# SCH_ATOM-Sumo_2026-06-13.net
KiCad netlist of a schematic drawn in EasyEDA
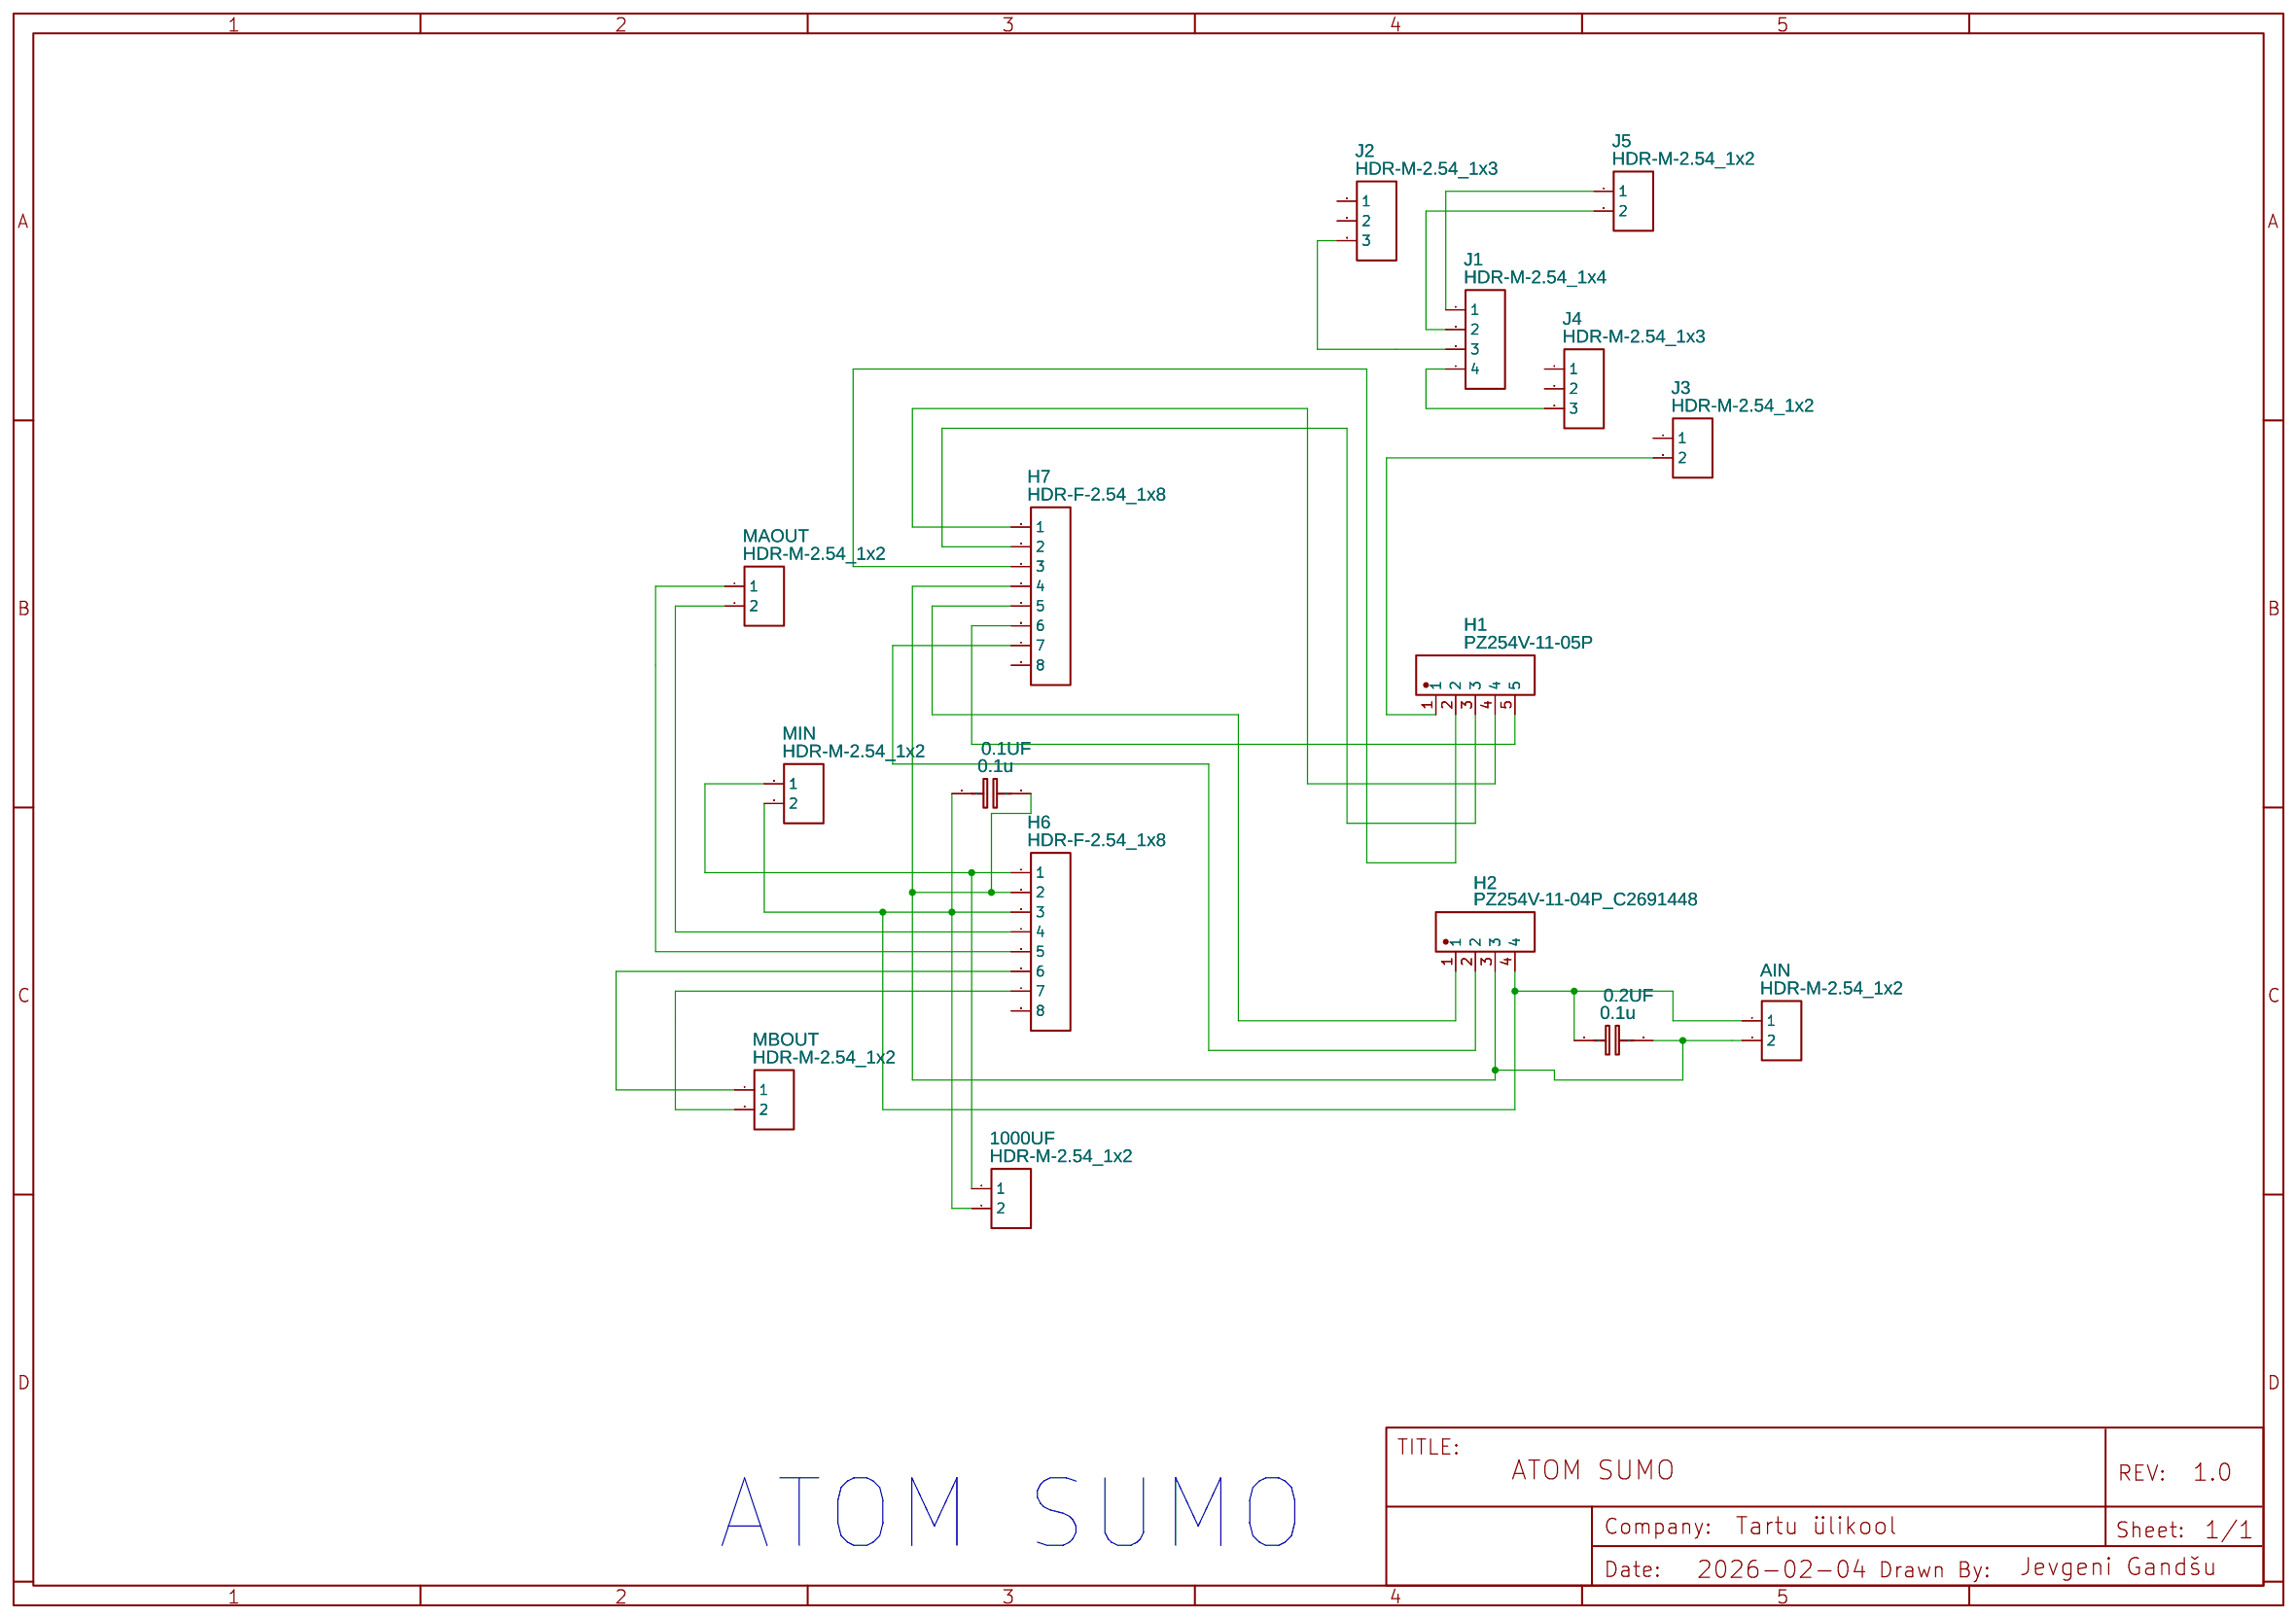
[diagram p0: schematic sheet]

(export (version "E")
  (design (tool "Eeschema 10.0.6"))
  (components
    (comp (ref "0.1UF") (value "0.1u") (libsource (lib "") (part "C_0805_EU")))
    (comp (ref "0.2UF") (value "0.1u") (libsource (lib "") (part "C_0805_EU_1")))
    (comp (ref "1000UF") (value "HDR-M-2.54_1x2") (libsource (lib "") (part "HDR-M-2.54_1x2_1")))
    (comp (ref "AIN") (value "HDR-M-2.54_1x2") (libsource (lib "") (part "HDR-M-2.54_1x2")))
    (comp (ref "H1")
      (value "PZ254V-11-05P")
      (fields (field (name "Manufacturer") "XFCN(兴飞)"))
      (libsource (lib "") (part "PZ254V-11-05P"))
    )
    (comp (ref "H2")
      (value "PZ254V-11-04P_C2691448")
      (fields (field (name "Manufacturer Part") "PZ254V-11-04P") (field (name "Manufacturer") "XFCN(兴飞)"))
      (libsource (lib "") (part "PZ254V-11-04P_C2691448"))
    )
    (comp (ref "H6") (value "HDR-F-2.54_1x8") (libsource (lib "") (part "HDR-F-2.54_1x8")))
    (comp (ref "H7") (value "HDR-F-2.54_1x8") (libsource (lib "") (part "HDR-F-2.54_1x8")))
    (comp (ref "J1") (value "HDR-M-2.54_1x4") (libsource (lib "") (part "HDR-M-2.54_1x4")))
    (comp (ref "J2") (value "HDR-M-2.54_1x3") (libsource (lib "") (part "HDR-M-2.54_1x3")))
    (comp (ref "J3") (value "HDR-M-2.54_1x2") (libsource (lib "") (part "HDR-M-2.54_1x2_3")))
    (comp (ref "J4") (value "HDR-M-2.54_1x3") (libsource (lib "") (part "HDR-M-2.54_1x3")))
    (comp (ref "J5") (value "HDR-M-2.54_1x2") (libsource (lib "") (part "HDR-M-2.54_1x2_3")))
    (comp (ref "MAOUT") (value "HDR-M-2.54_1x2") (libsource (lib "") (part "HDR-M-2.54_1x2_4")))
    (comp (ref "MBOUT") (value "HDR-M-2.54_1x2") (libsource (lib "") (part "HDR-M-2.54_1x2_2")))
    (comp (ref "MIN") (value "HDR-M-2.54_1x2") (libsource (lib "") (part "HDR-M-2.54_1x2_5")))
  )
  (nets
    (net (code "1") (name "Net-(0.1UF-Pad1)") (class "Default")
      (node (ref "0.1UF") (pin "1") (pinfunction "1_1") (pintype "unspecified"))
      (node (ref "0.2UF") (pin "1") (pinfunction "1_1") (pintype "unspecified"))
      (node (ref "1000UF") (pin "2") (pinfunction "2_2") (pintype "unspecified"))
      (node (ref "AIN") (pin "1") (pinfunction "1_1") (pintype "unspecified"))
      (node (ref "H2") (pin "4") (pinfunction "4_4") (pintype "unspecified"))
      (node (ref "H6") (pin "3") (pinfunction "3_3") (pintype "unspecified"))
      (node (ref "MIN") (pin "2") (pinfunction "2_2") (pintype "unspecified"))
    )
    (net (code "2") (name "Net-(0.1UF-Pad2)") (class "Default")
      (node (ref "0.1UF") (pin "2") (pinfunction "2_2") (pintype "unspecified"))
      (node (ref "0.2UF") (pin "2") (pinfunction "2_2") (pintype "unspecified"))
      (node (ref "AIN") (pin "2") (pinfunction "2_2") (pintype "unspecified"))
      (node (ref "H2") (pin "3") (pinfunction "3_3") (pintype "unspecified"))
      (node (ref "H6") (pin "2") (pinfunction "2_2") (pintype "unspecified"))
      (node (ref "H7") (pin "4") (pinfunction "4_4") (pintype "unspecified"))
    )
    (net (code "3") (name "Net-(1000UF-Pad1)") (class "Default")
      (node (ref "1000UF") (pin "1") (pinfunction "1_1") (pintype "unspecified"))
      (node (ref "H6") (pin "1") (pinfunction "1_1") (pintype "unspecified"))
      (node (ref "MIN") (pin "1") (pinfunction "1_1") (pintype "unspecified"))
    )
    (net (code "4") (name "Net-(H1-Pad1)") (class "Default")
      (node (ref "H1") (pin "1") (pinfunction "1_1") (pintype "unspecified"))
      (node (ref "J3") (pin "2") (pinfunction "2_2") (pintype "unspecified"))
    )
    (net (code "5") (name "Net-(H1-Pad2)") (class "Default")
      (node (ref "H1") (pin "2") (pinfunction "2_2") (pintype "unspecified"))
      (node (ref "H7") (pin "3") (pinfunction "3_3") (pintype "unspecified"))
    )
    (net (code "6") (name "Net-(H1-Pad3)") (class "Default")
      (node (ref "H1") (pin "3") (pinfunction "3_3") (pintype "unspecified"))
      (node (ref "H7") (pin "2") (pinfunction "2_2") (pintype "unspecified"))
    )
    (net (code "7") (name "Net-(H1-Pad4)") (class "Default")
      (node (ref "H1") (pin "4") (pinfunction "4_4") (pintype "unspecified"))
      (node (ref "H7") (pin "1") (pinfunction "1_1") (pintype "unspecified"))
    )
    (net (code "8") (name "Net-(H1-Pad5)") (class "Default")
      (node (ref "H1") (pin "5") (pinfunction "5_5") (pintype "unspecified"))
      (node (ref "H7") (pin "6") (pinfunction "6_6") (pintype "unspecified"))
    )
    (net (code "9") (name "Net-(H2-Pad1)") (class "Default")
      (node (ref "H2") (pin "1") (pinfunction "1_1") (pintype "unspecified"))
      (node (ref "H7") (pin "5") (pinfunction "5_5") (pintype "unspecified"))
    )
    (net (code "10") (name "Net-(H2-Pad2)") (class "Default")
      (node (ref "H2") (pin "2") (pinfunction "2_2") (pintype "unspecified"))
      (node (ref "H7") (pin "7") (pinfunction "7_7") (pintype "unspecified"))
    )
    (net (code "11") (name "Net-(H6-Pad4)") (class "Default")
      (node (ref "H6") (pin "4") (pinfunction "4_4") (pintype "unspecified"))
      (node (ref "MAOUT") (pin "2") (pinfunction "2_2") (pintype "unspecified"))
    )
    (net (code "12") (name "Net-(H6-Pad5)") (class "Default")
      (node (ref "H6") (pin "5") (pinfunction "5_5") (pintype "unspecified"))
      (node (ref "MAOUT") (pin "1") (pinfunction "1_1") (pintype "unspecified"))
    )
    (net (code "13") (name "Net-(H6-Pad6)") (class "Default")
      (node (ref "H6") (pin "6") (pinfunction "6_6") (pintype "unspecified"))
      (node (ref "MBOUT") (pin "1") (pinfunction "1_1") (pintype "unspecified"))
    )
    (net (code "14") (name "Net-(H6-Pad7)") (class "Default")
      (node (ref "H6") (pin "7") (pinfunction "7_7") (pintype "unspecified"))
      (node (ref "MBOUT") (pin "2") (pinfunction "2_2") (pintype "unspecified"))
    )
    (net (code "15") (name "Net-(J1-Pad1)") (class "Default")
      (node (ref "J1") (pin "1") (pinfunction "1_1") (pintype "unspecified"))
      (node (ref "J5") (pin "1") (pinfunction "1_1") (pintype "unspecified"))
    )
    (net (code "16") (name "Net-(J1-Pad2)") (class "Default")
      (node (ref "J1") (pin "2") (pinfunction "2_2") (pintype "unspecified"))
      (node (ref "J5") (pin "2") (pinfunction "2_2") (pintype "unspecified"))
    )
    (net (code "17") (name "Net-(J1-Pad3)") (class "Default")
      (node (ref "J1") (pin "3") (pinfunction "3_3") (pintype "unspecified"))
      (node (ref "J2") (pin "3") (pinfunction "3_3") (pintype "input"))
    )
    (net (code "18") (name "Net-(J1-Pad4)") (class "Default")
      (node (ref "J1") (pin "4") (pinfunction "4_4") (pintype "unspecified"))
      (node (ref "J4") (pin "3") (pinfunction "3_3") (pintype "input"))
    )
    (net (code "19") (name "unconnected-(H6-Pad8)") (class "Default")
      (node (ref "H6") (pin "8") (pinfunction "8_8") (pintype "unspecified"))
    )
    (net (code "20") (name "unconnected-(H7-Pad8)") (class "Default")
      (node (ref "H7") (pin "8") (pinfunction "8_8") (pintype "unspecified"))
    )
    (net (code "21") (name "unconnected-(J2-Pad1)") (class "Default")
      (node (ref "J2") (pin "1") (pinfunction "1_1") (pintype "input"))
    )
    (net (code "22") (name "unconnected-(J2-Pad2)") (class "Default")
      (node (ref "J2") (pin "2") (pinfunction "2_2") (pintype "input"))
    )
    (net (code "23") (name "unconnected-(J3-Pad1)") (class "Default")
      (node (ref "J3") (pin "1") (pinfunction "1_1") (pintype "unspecified"))
    )
    (net (code "24") (name "unconnected-(J4-Pad1)") (class "Default")
      (node (ref "J4") (pin "1") (pinfunction "1_1") (pintype "input"))
    )
    (net (code "25") (name "unconnected-(J4-Pad2)") (class "Default")
      (node (ref "J4") (pin "2") (pinfunction "2_2") (pintype "input"))
    )
  )
)
